# Booster_PA_PREAMP.net
KiCad netlist of a schematic drawn in Altium Designer
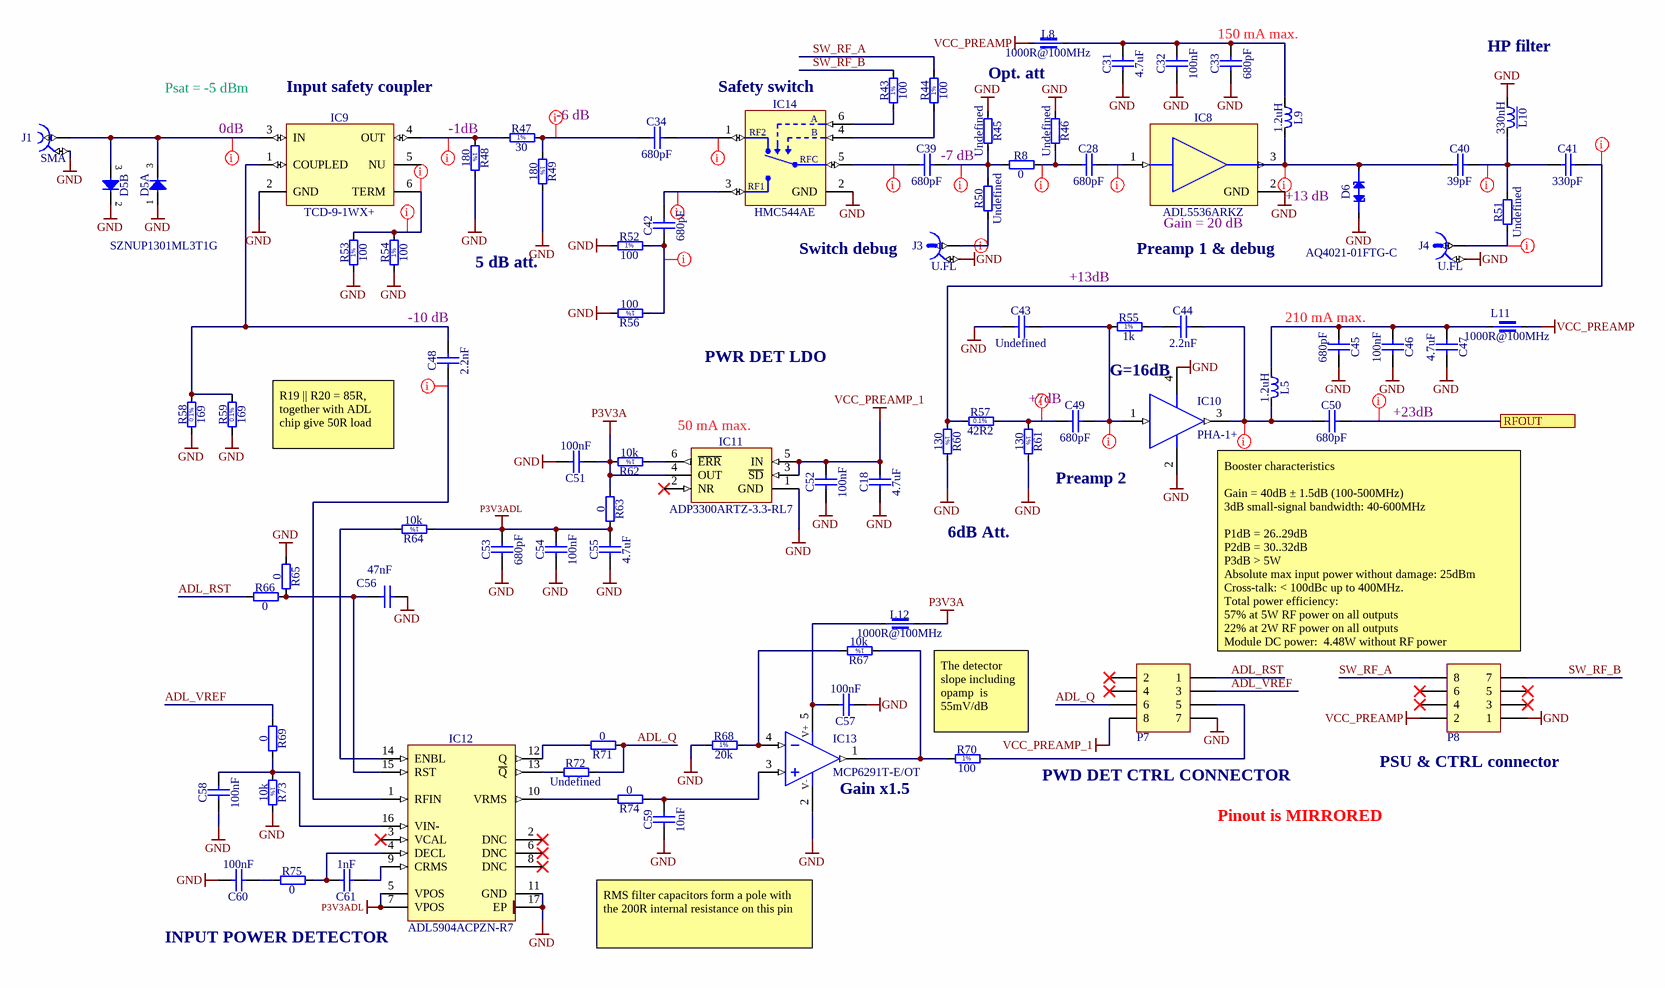
[diagram p0: Booster_PA_PREAMP.SchDoc]

(export (version "E")
  (design (tool "Eeschema 10.0.6"))
  (components
    (comp (ref "C18")
      (value "4.7uF")
      (footprint "CAPC1709X95N")
      (description "Non-polarised capacitor")
      (fields
        (field (name "MANUFACTURER") "GENERIC")
        (field (name "MANUFACTURER PART NUMBER") "CC0603_4.7UF_16V_10%_X5R")
        (field (name "AUTHOR") "CERN DEM JLC")
      )
      (libsource (lib "Capacitors") (part "Capacitor - non polarized"))
    )
    (comp (ref "C28")
      (value "680pF")
      (footprint "CAPC1608X87N")
      (description "Non-polarised capacitor")
      (fields
        (field (name "PART NUMBER") "CC0603_680PF_50V_5%_NP0")
        (field (name "VOLTAGE") "50V")
        (field (name "AUTHOR") "CERN DEM JLC")
      )
      (libsource (lib "Capacitors") (part "Capacitor - non polarized"))
    )
    (comp (ref "C31")
      (value "4.7uF")
      (footprint "CAPC1709X95N")
      (description "Non-polarised capacitor")
      (fields
        (field (name "MANUFACTURER") "GENERIC")
        (field (name "MANUFACTURER PART NUMBER") "CC0603_4.7UF_16V_10%_X5R")
        (field (name "AUTHOR") "CERN DEM JLC")
      )
      (libsource (lib "Capacitors") (part "Capacitor - non polarized"))
    )
    (comp (ref "C32")
      (value "100nF")
      (footprint "CAPC1608X87N")
      (description "Non-polarised capacitor")
      (fields
        (field (name "MANUFACTURER") "GENERIC")
        (field (name "MANUFACTURER PART NUMBER") "CC0603_100NF_50V_10%_X7R")
        (field (name "AUTHOR") "CERN DEM JLC")
      )
      (libsource (lib "Capacitors") (part "Capacitor - non polarized"))
    )
    (comp (ref "C33")
      (value "680pF")
      (footprint "CAPC1608X87N")
      (description "Non-polarised capacitor")
      (fields
        (field (name "PART NUMBER") "CC0603_680PF_50V_5%_NP0")
        (field (name "VOLTAGE") "50V")
        (field (name "AUTHOR") "CERN DEM JLC")
      )
      (libsource (lib "Capacitors") (part "Capacitor - non polarized"))
    )
    (comp (ref "C34")
      (value "680pF")
      (footprint "CAPC1608X87N")
      (description "Non-polarised capacitor")
      (fields
        (field (name "PART NUMBER") "CC0603_680PF_50V_5%_NP0")
        (field (name "VOLTAGE") "50V")
        (field (name "AUTHOR") "CERN DEM JLC")
      )
      (libsource (lib "Capacitors") (part "Capacitor - non polarized"))
    )
    (comp (ref "C39")
      (value "680pF")
      (footprint "CAPC1608X87N")
      (description "Non-polarised capacitor")
      (fields
        (field (name "PART NUMBER") "CC0603_680PF_50V_5%_NP0")
        (field (name "VOLTAGE") "50V")
        (field (name "AUTHOR") "CERN DEM JLC")
      )
      (libsource (lib "Capacitors") (part "Capacitor - non polarized"))
    )
    (comp (ref "C40")
      (value "39pF")
      (footprint "CAPC1608X87N")
      (description "Non-polarised capacitor")
      (fields
        (field (name "PART NUMBER") "CC0603_39PF_100V_1%_NP0")
        (field (name "VOLTAGE") "100V")
        (field (name "AUTHOR") "GK")
      )
      (libsource (lib "Passives_RC") (part "CC0603_39PF_50V_1%_NP0"))
    )
    (comp (ref "C41")
      (value "330pF")
      (footprint "CAPC1608X87N")
      (description "Non-polarised capacitor")
      (fields
        (field (name "MANUFACTURER") "GENERIC")
        (field (name "MANUFACTURER PART NUMBER") "CC0603_330PF_50V_1%_NP0")
        (field (name "AUTHOR") "CERN DEM MR")
      )
      (libsource (lib "Capacitors") (part "Capacitor - non polarized"))
    )
    (comp (ref "C42")
      (value "680pF")
      (footprint "CAPC1608X87N")
      (description "Non-polarised capacitor")
      (fields
        (field (name "PART NUMBER") "CC0603_680PF_50V_5%_NP0")
        (field (name "VOLTAGE") "50V")
        (field (name "AUTHOR") "CERN DEM JLC")
      )
      (libsource (lib "Capacitors") (part "Capacitor - non polarized"))
    )
    (comp (ref "C43")
      (value "Undefined")
      (footprint "CAPC1608X90N")
      (description "Non-polarised capacitor")
      (fields (field (name "PART NUMBER") "CC0603_NO-VALUE") (field (name "AUTHOR") "CERN DEM MR"))
      (libsource (lib "Capacitors") (part "Capacitor - non polarized"))
    )
    (comp (ref "C44")
      (value "2.2nF")
      (footprint "CAPC1608X87N")
      (description "Non-polarised capacitor")
      (fields
        (field (name "PART NUMBER") "CC0603_2.2NF_50V_5%_C0G")
        (field (name "VOLTAGE") "50V")
        (field (name "AUTHOR") "CERN DEM JMW")
      )
      (libsource (lib "Capacitors") (part "Capacitor - non polarized"))
    )
    (comp (ref "C45")
      (value "680pF")
      (footprint "CAPC1608X87N")
      (description "Non-polarised capacitor")
      (fields
        (field (name "MANUFACTURER") "GENERIC")
        (field (name "MANUFACTURER PART NUMBER") "CC0603_680PF_50V_5%_NP0")
        (field (name "AUTHOR") "CERN DEM JLC")
      )
      (libsource (lib "Capacitors") (part "Capacitor - non polarized"))
    )
    (comp (ref "C46")
      (value "100nF")
      (footprint "CAPC1608X87N")
      (description "Non-polarised capacitor")
      (fields
        (field (name "MANUFACTURER") "GENERIC")
        (field (name "MANUFACTURER PART NUMBER") "CC0603_100NF_50V_10%_X7R")
        (field (name "AUTHOR") "CERN DEM JLC")
      )
      (libsource (lib "Capacitors") (part "Capacitor - non polarized"))
    )
    (comp (ref "C47")
      (value "4.7uF")
      (footprint "CAPC1709X95N")
      (description "Non-polarised capacitor")
      (fields
        (field (name "MANUFACTURER") "GENERIC")
        (field (name "MANUFACTURER PART NUMBER") "CC0603_4.7UF_16V_10%_X5R")
        (field (name "AUTHOR") "CERN DEM JLC")
      )
      (libsource (lib "Capacitors") (part "Capacitor - non polarized"))
    )
    (comp (ref "C48")
      (value "2.2nF")
      (footprint "CAPC1608X87N")
      (description "Non-polarised capacitor")
      (fields
        (field (name "PART NUMBER") "CC0603_2.2NF_50V_5%_C0G")
        (field (name "VOLTAGE") "50V")
        (field (name "AUTHOR") "CERN DEM JMW")
      )
      (libsource (lib "Capacitors") (part "Capacitor - non polarized"))
    )
    (comp (ref "C49")
      (value "680pF")
      (footprint "CAPC1608X87N")
      (description "Non-polarised capacitor")
      (fields
        (field (name "MANUFACTURER") "GENERIC")
        (field (name "MANUFACTURER PART NUMBER") "CC0603_680PF_50V_5%_NP0")
        (field (name "AUTHOR") "CERN DEM JLC")
      )
      (libsource (lib "Capacitors") (part "Capacitor - non polarized"))
    )
    (comp (ref "C50")
      (value "680pF")
      (footprint "CAPC1608X87N")
      (description "Non-polarised capacitor")
      (fields
        (field (name "MANUFACTURER") "GENERIC")
        (field (name "MANUFACTURER PART NUMBER") "CC0603_680PF_50V_5%_NP0")
        (field (name "AUTHOR") "CERN DEM JLC")
      )
      (libsource (lib "Capacitors") (part "Capacitor - non polarized"))
    )
    (comp (ref "C51")
      (value "100nF")
      (footprint "CAPC1608X87N")
      (description "Non-polarised capacitor")
      (fields
        (field (name "MANUFACTURER") "GENERIC")
        (field (name "MANUFACTURER PART NUMBER") "CC0603_100NF_50V_10%_X7R")
        (field (name "AUTHOR") "CERN DEM JLC")
      )
      (libsource (lib "Capacitors") (part "Capacitor - non polarized"))
    )
    (comp (ref "C52")
      (value "100nF")
      (footprint "CAPC1608X87N")
      (description "Non-polarised capacitor")
      (fields
        (field (name "MANUFACTURER") "GENERIC")
        (field (name "MANUFACTURER PART NUMBER") "CC0603_100NF_50V_10%_X7R")
        (field (name "AUTHOR") "CERN DEM JLC")
      )
      (libsource (lib "Capacitors") (part "Capacitor - non polarized"))
    )
    (comp (ref "C53")
      (value "680pF")
      (footprint "CAPC1608X87N")
      (description "Non-polarised capacitor")
      (fields
        (field (name "MANUFACTURER") "GENERIC")
        (field (name "MANUFACTURER PART NUMBER") "CC0603_680PF_50V_5%_NP0")
        (field (name "AUTHOR") "CERN DEM JLC")
      )
      (libsource (lib "Capacitors") (part "Capacitor - non polarized"))
    )
    (comp (ref "C54")
      (value "100nF")
      (footprint "CAPC1608X87N")
      (description "Non-polarised capacitor")
      (fields
        (field (name "MANUFACTURER") "GENERIC")
        (field (name "MANUFACTURER PART NUMBER") "CC0603_100NF_50V_10%_X7R")
        (field (name "AUTHOR") "CERN DEM JLC")
      )
      (libsource (lib "Capacitors") (part "Capacitor - non polarized"))
    )
    (comp (ref "C55")
      (value "4.7uF")
      (footprint "CAPC1709X95N")
      (description "Non-polarised capacitor")
      (fields
        (field (name "MANUFACTURER") "GENERIC")
        (field (name "MANUFACTURER PART NUMBER") "CC0603_4.7UF_16V_10%_X5R")
        (field (name "AUTHOR") "CERN DEM JLC")
      )
      (libsource (lib "Capacitors") (part "Capacitor - non polarized"))
    )
    (comp (ref "C56")
      (value "47nF")
      (footprint "CAPC1608X87N")
      (description "Non-polarised capacitor")
      (fields
        (field (name "PART NUMBER") "CC0603_47NF_25V_10%_X7R")
        (field (name "VOLTAGE") "25V")
        (field (name "AUTHOR") "CERN DEM JLC")
      )
      (libsource (lib "Capacitors") (part "Capacitor - non polarized"))
    )
    (comp (ref "C57")
      (value "100nF")
      (footprint "CAPC1608X87N")
      (description "Non-polarised capacitor")
      (fields
        (field (name "MANUFACTURER") "GENERIC")
        (field (name "MANUFACTURER PART NUMBER") "CC0603_100NF_50V_10%_X7R")
        (field (name "AUTHOR") "CERN DEM JLC")
      )
      (libsource (lib "Capacitors") (part "Capacitor - non polarized"))
    )
    (comp (ref "C58")
      (value "100nF")
      (footprint "CAPC1608X87N")
      (description "Non-polarised capacitor")
      (fields
        (field (name "MANUFACTURER") "GENERIC")
        (field (name "MANUFACTURER PART NUMBER") "CC0603_100NF_50V_10%_X7R")
        (field (name "AUTHOR") "CERN DEM JLC")
      )
      (libsource (lib "Capacitors") (part "Capacitor - non polarized"))
    )
    (comp (ref "C59")
      (value "10nF")
      (footprint "CAPC1005X55N")
      (description "Non-polarised capacitor")
      (fields
        (field (name "MANUFACTURER") "GENERIC")
        (field (name "MANUFACTURER PART NUMBER") "CC0402_10NF_25V_10%_X7R")
        (field (name "AUTHOR") "CERN DEM JLC")
      )
      (libsource (lib "Capacitors") (part "Capacitor - non polarized"))
    )
    (comp (ref "C60")
      (value "100nF")
      (footprint "CAPC1608X87N")
      (description "Non-polarised capacitor")
      (fields
        (field (name "MANUFACTURER") "GENERIC")
        (field (name "MANUFACTURER PART NUMBER") "CC0603_100NF_50V_10%_X7R")
        (field (name "AUTHOR") "CERN DEM JLC")
      )
      (libsource (lib "Capacitors") (part "Capacitor - non polarized"))
    )
    (comp (ref "C61")
      (value "1nF")
      (footprint "CAPC1005X55N")
      (description "Non-polarised capacitor")
      (fields
        (field (name "PART NUMBER") "CC0402_1NF_50V_10%_X7R")
        (field (name "VOLTAGE") "50V")
        (field (name "AUTHOR") "CERN DEM JLC")
      )
      (libsource (lib "Capacitors") (part "Capacitor - non polarized"))
    )
    (comp (ref "D5")
      (value "SZNUP1301ML3T1G")
      (footprint "SOT95P240X110-3N")
      (description "Low Capacitance Diode Array for ESD Protection in a Single Data Line")
      (fields (field (name "VOLTAGE") "70V") (field (name "POWER") "215mA") (field (name "AUTHOR") "GK"))
      (libsource (lib "Diodes") (part "D_TVS_SZNUP1301ML3T1G"))
    )
    (comp (ref "D6")
      (value "AQ4021-01FTG-C")
      (footprint "SOD2513X114N")
      (description "6V Bi-directional,ESD Protection for Transient Voltage Suppressor Diode")
      (fields (field (name "VOLTAGE") "6V") (field (name "POWER") "450W") (field (name "AUTHOR") "GK"))
      (libsource (lib "Diodes") (part "D_TVS_AQ4021-01FTG-C"))
    )
    (comp (ref "IC8")
      (value "ADL5536ARKZ")
      (footprint "ANALOG-DEVICES_SOT-89(RK-3)")
      (description "20MHz to 1GHz IF Gain Block")
      (fields (field (name "MANUFACTURER") "ANALOG DEVICES") (field (name "AUTHOR") "CERN DEM BC"))
      (libsource (lib "ICs And Semiconductors") (part "ADL5536"))
    )
    (comp (ref "IC9")
      (value "TCD-9-1WX+")
      (footprint "MINI-CIRCUITS_DB1627")
      (description "50 Ohm, 5 To 2000MHz, Directional Coupler")
      (fields (field (name "MANUFACTURER") "MINI-CIRCUITS") (field (name "AUTHOR") "CERN DEM BC"))
      (libsource (lib "ICs And Semiconductors") (part "TCD-9-1W"))
    )
    (comp (ref "IC10")
      (value "PHA-1+")
      (footprint "MINI-CIRCUITS_DF782")
      (description "Monolithic Amplifier")
      (fields (field (name "MANUFACTURER") "MINI-CIRCUITS") (field (name "AUTHOR") "CERN DEM BC"))
      (libsource (lib "ICs And Semiconductors") (part "Monolithic Amplifier Type 1"))
    )
    (comp (ref "IC11")
      (value "ADP3300ARTZ-3.3-RL7")
      (footprint "SOT95P280X145-6N")
      (description "High Accuracy anyCAP® 50 mA Low Dropout Linear Regulator")
      (fields (field (name "MANUFACTURER") "ANALOG DEVICES") (field (name "AUTHOR") "CERN DEM JLC"))
      (libsource (lib "ICs And Semiconductors") (part "ADP3300ARTZ"))
    )
    (comp (ref "IC12")
      (value "ADL5904ACPZN-R7")
      (footprint "QFN50P300X300X80-17N-S175")
      (description "DC to 6 GHz, 45 dB TruPwr Detector With Envelope Threshold Detection")
      (fields (field (name "MANUFACTURER") "ANALOG DEVICES") (field (name "AUTHOR") "CERN DEM MR"))
      (libsource (lib "ICs And Semiconductors") (part "ADL5904"))
    )
    (comp (ref "IC13")
      (value "MCP6291T-E/OT")
      (footprint "SOT95P270X145-5N")
      (description "Operational Amplifier")
      (fields (field (name "MANUFACTURER") "MICROCHIP TECHNOLOGY") (field (name "AUTHOR") "CERN DEM BC"))
      (libsource (lib "ICs And Semiconductors") (part "Operational Amplifier Type7"))
    )
    (comp (ref "IC14")
      (value "HMC544AE")
      (footprint "SOT95P280X145-6N")
      (description "GaAs MMIC T/R Switch DC - 4 GHz")
      (fields (field (name "MANUFACTURER") "ANALOG DEVICES") (field (name "AUTHOR") "CERN DEM MR"))
      (libsource (lib "ICs And Semiconductors") (part "HMC544AE"))
    )
    (comp (ref "J1")
      (value "SMA")
      (footprint "LINK_CONSMA002-SMD-G")
      (fields
        (field (name "PART NUMBER") "LINK_CONSMA002-SMD-G")
        (field (name "MANUFACTURER") "LINK TECHNOLOGIES")
        (field (name "MANUFACTURER PART NUMBER") "CONSMA002-SMD-G")
        (field (name "AUTHOR") "CERN DEM BC")
      )
      (libsource (lib "Connectors") (part "Coax_1Female_1Shield"))
    )
    (comp (ref "J3")
      (value "U.FL")
      (footprint "HIROSE_U.FL-R-SMT-1(10)")
      (fields
        (field (name "PART NUMBER") "HIROSE_U.FL-R-SMT-1(10)")
        (field (name "MANUFACTURER") "HIROSE (HRS)")
        (field (name "MANUFACTURER PART NUMBER") "U.FL-R-SMT-1(10)")
        (field (name "AUTHOR") "CERN DEM JLC")
      )
      (libsource (lib "Connectors") (part "Coax_1Male_1Shield"))
    )
    (comp (ref "J4")
      (value "U.FL")
      (footprint "HIROSE_U.FL-R-SMT-1(10)")
      (fields
        (field (name "PART NUMBER") "HIROSE_U.FL-R-SMT-1(10)")
        (field (name "MANUFACTURER") "HIROSE (HRS)")
        (field (name "MANUFACTURER PART NUMBER") "U.FL-R-SMT-1(10)")
        (field (name "AUTHOR") "CERN DEM JLC")
      )
      (libsource (lib "Connectors") (part "Coax_1Male_1Shield"))
    )
    (comp (ref "L5")
      (value "1.2uH")
      (footprint "IND_TDK_ADL2012")
      (description "Inductor")
      (fields
        (field (name "PART NUMBER") "IND0805_TDK_ADL2012S-1R2M-T01")
        (field (name "POWER") "400mA")
        (field (name "AUTHOR") "GK")
      )
      (libsource (lib "Inductors_Transformers") (part "IND0805_TDK_ADL2012S-1R2M-T01"))
    )
    (comp (ref "L8")
      (value "1000R@100MHz")
      (footprint "INDC1608X95N")
      (fields
        (field (name "MANUFACTURER") "MURATA")
        (field (name "MANUFACTURER PART NUMBER") "BLM18HE102SN1")
        (field (name "PART NUMBER") "IND0603_MURATA_BLM18HE102SN1")
        (field (name "AUTHOR") "CERN DEM JLC")
      )
      (libsource (lib "Inductors & Transformers") (part "Ferrite Bead"))
    )
    (comp (ref "L9")
      (value "1.2uH")
      (footprint "IND_TDK_ADL2012")
      (description "Inductor")
      (fields
        (field (name "PART NUMBER") "IND0805_TDK_ADL2012S-1R2M-T01")
        (field (name "POWER") "400mA")
        (field (name "AUTHOR") "GK")
      )
      (libsource (lib "Inductors_Transformers") (part "IND0805_TDK_ADL2012S-1R2M-T01"))
    )
    (comp (ref "L10")
      (value "330nH")
      (footprint "IND_COILCRAFT_0603LS")
      (description "Inductor With Core")
      (fields
        (field (name "PART NUMBER") "IND_330NH_2%_COILCRAFT_0603LS")
        (field (name "POWER") "560mA")
        (field (name "AUTHOR") "CERN DEM BC")
      )
      (libsource (lib "Inductors & Transformers") (part "Inductor With Magnetic core"))
    )
    (comp (ref "L11")
      (value "1000R@100MHz")
      (footprint "INDC1608X95N")
      (fields
        (field (name "MANUFACTURER") "MURATA")
        (field (name "MANUFACTURER PART NUMBER") "BLM18HE102SN1")
        (field (name "PART NUMBER") "IND0603_MURATA_BLM18HE102SN1")
        (field (name "AUTHOR") "CERN DEM JLC")
      )
      (libsource (lib "Inductors & Transformers") (part "Ferrite Bead"))
    )
    (comp (ref "L12")
      (value "1000R@100MHz")
      (footprint "INDC1608X95N")
      (fields
        (field (name "MANUFACTURER") "MURATA")
        (field (name "MANUFACTURER PART NUMBER") "BLM18HE102SN1")
        (field (name "PART NUMBER") "IND0603_MURATA_BLM18HE102SN1")
        (field (name "AUTHOR") "CERN DEM JLC")
      )
      (libsource (lib "Inductors & Transformers") (part "Ferrite Bead"))
    )
    (comp (ref "P7")
      (value "ZL264-8DG")
      (footprint "HDR2X4_SMD")
      (description "Header, 4-Pin, Dual Row")
      (libsource (lib "onyks") (part "HDR2X4"))
    )
    (comp (ref "P8")
      (value "ZL264-8DG")
      (footprint "HDR2X4_SMD")
      (description "Header, 4-Pin, Dual Row")
      (libsource (lib "") (part "HDR2X4_1"))
    )
    (comp (ref "R8")
      (value "0")
      (footprint "RESC1005X40N")
      (description "Resistor")
      (fields
        (field (name "MANUFACTURER") "GENERIC")
        (field (name "MANUFACTURER PART NUMBER") "R0402_0R_JUMPER")
        (field (name "AUTHOR") "CERN DEM JLC")
      )
      (libsource (lib "Resistors") (part "Resistor"))
    )
    (comp (ref "R43")
      (value "100")
      (footprint "RESC1608X55N")
      (description "Resistor - 1%")
      (fields
        (field (name "MANUFACTURER") "GENERIC")
        (field (name "MANUFACTURER PART NUMBER") "R0603_100R_1%_0.1W_100PPM")
        (field (name "AUTHOR") "CERN DEM JLC")
      )
      (libsource (lib "Resistors") (part "Resistor - 1%"))
    )
    (comp (ref "R44")
      (value "100")
      (footprint "RESC1608X55N")
      (description "Resistor - 1%")
      (fields
        (field (name "MANUFACTURER") "GENERIC")
        (field (name "MANUFACTURER PART NUMBER") "R0603_100R_1%_0.1W_100PPM")
        (field (name "AUTHOR") "CERN DEM JLC")
      )
      (libsource (lib "Resistors") (part "Resistor - 1%"))
    )
    (comp (ref "R45")
      (value "Undefined")
      (footprint "RESC1608X55N")
      (description "Resistor")
      (fields
        (field (name "MANUFACTURER PART NUMBER") "R0603_NO-VALUE")
        (field (name "AUTHOR") "CERN DEM JLC")
      )
      (libsource (lib "Resistors") (part "Resistor"))
    )
    (comp (ref "R46")
      (value "Undefined")
      (footprint "RESC1608X55N")
      (description "Resistor")
      (fields
        (field (name "MANUFACTURER PART NUMBER") "R0603_NO-VALUE")
        (field (name "AUTHOR") "CERN DEM JLC")
      )
      (libsource (lib "Resistors") (part "Resistor"))
    )
    (comp (ref "R47")
      (value "30")
      (footprint "RESC1608X55N")
      (description "Resistor - 1%")
      (fields
        (field (name "PART NUMBER") "R0603_30R_1%_0.1W_100PPM")
        (field (name "POWER") "0.1W")
        (field (name "AUTHOR") "CERN DEM JLC")
      )
      (libsource (lib "Resistors") (part "Resistor - 1%"))
    )
    (comp (ref "R48")
      (value "180")
      (footprint "RESC1608X55N")
      (description "Resistor - 1%")
      (fields
        (field (name "MANUFACTURER") "GENERIC")
        (field (name "MANUFACTURER PART NUMBER") "R0603_180R_1%_0.1W_100PPM")
        (field (name "AUTHOR") "CERN DEM JLC")
      )
      (libsource (lib "Resistors") (part "Resistor - 1%"))
    )
    (comp (ref "R49")
      (value "180")
      (footprint "RESC1608X55N")
      (description "Resistor - 1%")
      (fields
        (field (name "MANUFACTURER") "GENERIC")
        (field (name "MANUFACTURER PART NUMBER") "R0603_180R_1%_0.1W_100PPM")
        (field (name "AUTHOR") "CERN DEM JLC")
      )
      (libsource (lib "Resistors") (part "Resistor - 1%"))
    )
    (comp (ref "R50")
      (value "Undefined")
      (footprint "RESC1608X55N")
      (description "Resistor")
      (fields
        (field (name "MANUFACTURER PART NUMBER") "R0603_NO-VALUE")
        (field (name "AUTHOR") "CERN DEM JLC")
      )
      (libsource (lib "Resistors") (part "Resistor"))
    )
    (comp (ref "R51")
      (value "Undefined")
      (footprint "RESC1608X55N")
      (description "Resistor")
      (fields
        (field (name "MANUFACTURER PART NUMBER") "R0603_NO-VALUE")
        (field (name "AUTHOR") "CERN DEM JLC")
      )
      (libsource (lib "Resistors") (part "Resistor"))
    )
    (comp (ref "R52")
      (value "100")
      (footprint "RESC1608X55N")
      (description "Resistor - 1%")
      (fields
        (field (name "MANUFACTURER") "GENERIC")
        (field (name "MANUFACTURER PART NUMBER") "R0603_100R_1%_0.1W_100PPM")
        (field (name "AUTHOR") "CERN DEM JLC")
      )
      (libsource (lib "Resistors") (part "Resistor - 1%"))
    )
    (comp (ref "R53")
      (value "100")
      (footprint "RESC1608X55N")
      (description "Resistor - 1%")
      (fields
        (field (name "MANUFACTURER") "GENERIC")
        (field (name "MANUFACTURER PART NUMBER") "R0603_100R_1%_0.1W_100PPM")
        (field (name "AUTHOR") "CERN DEM JLC")
      )
      (libsource (lib "Resistors") (part "Resistor - 1%"))
    )
    (comp (ref "R54")
      (value "100")
      (footprint "RESC1608X55N")
      (description "Resistor - 1%")
      (fields
        (field (name "MANUFACTURER") "GENERIC")
        (field (name "MANUFACTURER PART NUMBER") "R0603_100R_1%_0.1W_100PPM")
        (field (name "AUTHOR") "CERN DEM JLC")
      )
      (libsource (lib "Resistors") (part "Resistor - 1%"))
    )
    (comp (ref "R55")
      (value "1k")
      (footprint "RESC1608X55N")
      (description "Resistor - 1%")
      (fields
        (field (name "MANUFACTURER") "GENERIC")
        (field (name "MANUFACTURER PART NUMBER") "R0603_1K_1%_0.1W_100PPM")
        (field (name "AUTHOR") "CERN DEM JLC")
      )
      (libsource (lib "Resistors") (part "Resistor - 1%"))
    )
    (comp (ref "R56")
      (value "100")
      (footprint "RESC1608X55N")
      (description "Resistor - 1%")
      (fields
        (field (name "MANUFACTURER") "GENERIC")
        (field (name "MANUFACTURER PART NUMBER") "R0603_100R_1%_0.1W_100PPM")
        (field (name "AUTHOR") "CERN DEM JLC")
      )
      (libsource (lib "Resistors") (part "Resistor - 1%"))
    )
    (comp (ref "R57")
      (value "42R2")
      (footprint "RESC1608X55N")
      (description "Resistor - 0.1%")
      (fields
        (field (name "PART NUMBER") "R0603_42R2_0.1%_0.063W_10PPM")
        (field (name "POWER") "0.063W")
        (field (name "AUTHOR") "CERN DEM JLC")
      )
      (libsource (lib "Resistors") (part "Resistor - 0.1%"))
    )
    (comp (ref "R58")
      (value "169")
      (footprint "RESC1608X55N")
      (description "Resistor - 0.1%")
      (fields
        (field (name "PART NUMBER") "R0603_169R_0.1%_0.063W_10PPM")
        (field (name "POWER") "0.063W")
        (field (name "AUTHOR") "CERN DEM JLC")
      )
      (libsource (lib "Resistors") (part "Resistor - 0.1%"))
    )
    (comp (ref "R59")
      (value "169")
      (footprint "RESC1608X55N")
      (description "Resistor - 0.1%")
      (fields
        (field (name "PART NUMBER") "R0603_169R_0.1%_0.063W_10PPM")
        (field (name "POWER") "0.063W")
        (field (name "AUTHOR") "CERN DEM JLC")
      )
      (libsource (lib "Resistors") (part "Resistor - 0.1%"))
    )
    (comp (ref "R60")
      (value "130")
      (footprint "RESC1608X55N")
      (description "Resistor - 1%")
      (fields
        (field (name "MANUFACTURER") "GENERIC")
        (field (name "MANUFACTURER PART NUMBER") "R0603_130R_1%_0.1W_100PPM")
        (field (name "AUTHOR") "CERN DEM JLC")
      )
      (libsource (lib "Resistors") (part "Resistor - 1%"))
    )
    (comp (ref "R61")
      (value "130")
      (footprint "RESC1608X55N")
      (description "Resistor - 1%")
      (fields
        (field (name "MANUFACTURER") "GENERIC")
        (field (name "MANUFACTURER PART NUMBER") "R0603_130R_1%_0.1W_100PPM")
        (field (name "AUTHOR") "CERN DEM JLC")
      )
      (libsource (lib "Resistors") (part "Resistor - 1%"))
    )
    (comp (ref "R62")
      (value "10k")
      (footprint "RESC1005X40N")
      (description "Resistor - 1%")
      (fields
        (field (name "MANUFACTURER") "GENERIC")
        (field (name "MANUFACTURER PART NUMBER") "R0402_10K_1%_0.0625W_100PPM")
        (field (name "AUTHOR") "CERN DEM JLC")
      )
      (libsource (lib "Resistors") (part "Resistor - 1%"))
    )
    (comp (ref "R63")
      (value "0")
      (footprint "RESC1005X40N")
      (description "Resistor")
      (fields
        (field (name "MANUFACTURER") "GENERIC")
        (field (name "MANUFACTURER PART NUMBER") "R0402_0R_JUMPER")
        (field (name "AUTHOR") "CERN DEM JLC")
      )
      (libsource (lib "Resistors") (part "Resistor"))
    )
    (comp (ref "R64")
      (value "10k")
      (footprint "RESC1005X40N")
      (description "Resistor - 1%")
      (fields
        (field (name "MANUFACTURER") "GENERIC")
        (field (name "MANUFACTURER PART NUMBER") "R0402_10K_1%_0.0625W_100PPM")
        (field (name "AUTHOR") "CERN DEM JLC")
      )
      (libsource (lib "Resistors") (part "Resistor - 1%"))
    )
    (comp (ref "R65")
      (value "0")
      (footprint "RESC1005X40N")
      (description "Resistor")
      (fields
        (field (name "MANUFACTURER") "GENERIC")
        (field (name "MANUFACTURER PART NUMBER") "R0402_0R_JUMPER")
        (field (name "AUTHOR") "CERN DEM JLC")
      )
      (libsource (lib "Resistors") (part "Resistor"))
    )
    (comp (ref "R66")
      (value "0")
      (footprint "RESC1005X40N")
      (description "Resistor")
      (fields
        (field (name "MANUFACTURER") "GENERIC")
        (field (name "MANUFACTURER PART NUMBER") "R0402_0R_JUMPER")
        (field (name "AUTHOR") "CERN DEM JLC")
      )
      (libsource (lib "Resistors") (part "Resistor"))
    )
    (comp (ref "R67")
      (value "10k")
      (footprint "RESC1005X40N")
      (description "Resistor - 1%")
      (fields
        (field (name "MANUFACTURER") "GENERIC")
        (field (name "MANUFACTURER PART NUMBER") "R0402_10K_1%_0.0625W_100PPM")
        (field (name "AUTHOR") "CERN DEM JLC")
      )
      (libsource (lib "Resistors") (part "Resistor - 1%"))
    )
    (comp (ref "R68")
      (value "20k")
      (footprint "RESC1608X55N")
      (description "Resistor - 1%")
      (fields
        (field (name "PART NUMBER") "R0603_20K_1%_0.1W_100PPM")
        (field (name "POWER") "0.1W")
        (field (name "AUTHOR") "CERN DEM JLC")
      )
      (libsource (lib "Resistors") (part "Resistor - 1%"))
    )
    (comp (ref "R69")
      (value "0")
      (footprint "RESC1005X40N")
      (description "Resistor")
      (fields
        (field (name "MANUFACTURER") "GENERIC")
        (field (name "MANUFACTURER PART NUMBER") "R0402_0R_JUMPER")
        (field (name "AUTHOR") "CERN DEM JLC")
      )
      (libsource (lib "Resistors") (part "Resistor"))
    )
    (comp (ref "R70")
      (value "100")
      (footprint "RESC1608X55N")
      (description "Resistor - 1%")
      (fields
        (field (name "MANUFACTURER") "GENERIC")
        (field (name "MANUFACTURER PART NUMBER") "R0603_100R_1%_0.1W_100PPM")
        (field (name "AUTHOR") "CERN DEM JLC")
      )
      (libsource (lib "Resistors") (part "Resistor - 1%"))
    )
    (comp (ref "R71")
      (value "0")
      (footprint "RESC1005X40N")
      (description "Resistor")
      (fields
        (field (name "MANUFACTURER") "GENERIC")
        (field (name "MANUFACTURER PART NUMBER") "R0402_0R_JUMPER")
        (field (name "AUTHOR") "CERN DEM JLC")
      )
      (libsource (lib "Resistors") (part "Resistor"))
    )
    (comp (ref "R72")
      (value "Undefined")
      (footprint "RESC1608X55N")
      (description "Resistor")
      (fields
        (field (name "MANUFACTURER PART NUMBER") "R0603_NO-VALUE")
        (field (name "AUTHOR") "CERN DEM JLC")
      )
      (libsource (lib "Resistors") (part "Resistor"))
    )
    (comp (ref "R73")
      (value "10k")
      (footprint "RESC1005X40N")
      (description "Resistor - 1%")
      (fields
        (field (name "MANUFACTURER") "GENERIC")
        (field (name "MANUFACTURER PART NUMBER") "R0402_10K_1%_0.0625W_100PPM")
        (field (name "AUTHOR") "CERN DEM JLC")
      )
      (libsource (lib "Resistors") (part "Resistor - 1%"))
    )
    (comp (ref "R74")
      (value "0")
      (footprint "RESC1005X40N")
      (description "Resistor")
      (fields
        (field (name "MANUFACTURER") "GENERIC")
        (field (name "MANUFACTURER PART NUMBER") "R0402_0R_JUMPER")
        (field (name "AUTHOR") "CERN DEM JLC")
      )
      (libsource (lib "Resistors") (part "Resistor"))
    )
    (comp (ref "R75")
      (value "0")
      (footprint "RESC1005X40N")
      (description "Resistor")
      (fields
        (field (name "MANUFACTURER") "GENERIC")
        (field (name "MANUFACTURER PART NUMBER") "R0402_0R_JUMPER")
        (field (name "AUTHOR") "CERN DEM JLC")
      )
      (libsource (lib "Resistors") (part "Resistor"))
    )
  )
  (nets
    (net (code "1") (name "/ADL_Q") (class "Default")
      (node (ref "P7") (pin "6") (pinfunction "6_6") (pintype "passive"))
      (node (ref "R71") (pin "1") (pinfunction "1_1") (pintype "passive"))
      (node (ref "R72") (pin "2") (pinfunction "2_2") (pintype "passive"))
    )
    (net (code "2") (name "/ADL_RST") (class "Default")
      (node (ref "P7") (pin "1") (pinfunction "1_1") (pintype "passive"))
      (node (ref "R66") (pin "1") (pinfunction "1_1") (pintype "passive"))
    )
    (net (code "3") (name "/ADL_VREF") (class "Default")
      (node (ref "P7") (pin "3") (pinfunction "3_3") (pintype "passive"))
      (node (ref "R69") (pin "1") (pinfunction "1_1") (pintype "passive"))
    )
    (net (code "4") (name "/RFOUT") (class "Default")
      (node (ref "C50") (pin "2") (pinfunction "2_2") (pintype "passive"))
    )
    (net (code "5") (name "/SW_RF_A") (class "Default")
      (node (ref "P8") (pin "8") (pinfunction "8_8") (pintype "passive"))
      (node (ref "R44") (pin "2") (pinfunction "2_2") (pintype "passive"))
    )
    (net (code "6") (name "/SW_RF_B") (class "Default")
      (node (ref "P8") (pin "7") (pinfunction "7_7") (pintype "passive"))
      (node (ref "R43") (pin "2") (pinfunction "2_2") (pintype "passive"))
    )
    (net (code "7") (name "GND") (class "Default")
      (node (ref "C18") (pin "1") (pinfunction "1_1") (pintype "passive"))
      (node (ref "C31") (pin "1") (pinfunction "1_1") (pintype "passive"))
      (node (ref "C32") (pin "1") (pinfunction "1_1") (pintype "passive"))
      (node (ref "C33") (pin "1") (pinfunction "1_1") (pintype "passive"))
      (node (ref "C43") (pin "1") (pinfunction "1_1") (pintype "passive"))
      (node (ref "C45") (pin "1") (pinfunction "1_1") (pintype "passive"))
      (node (ref "C46") (pin "1") (pinfunction "1_1") (pintype "passive"))
      (node (ref "C47") (pin "1") (pinfunction "1_1") (pintype "passive"))
      (node (ref "C51") (pin "2") (pinfunction "2_2") (pintype "passive"))
      (node (ref "C52") (pin "1") (pinfunction "1_1") (pintype "passive"))
      (node (ref "C53") (pin "1") (pinfunction "1_1") (pintype "passive"))
      (node (ref "C54") (pin "1") (pinfunction "1_1") (pintype "passive"))
      (node (ref "C55") (pin "1") (pinfunction "1_1") (pintype "passive"))
      (node (ref "C56") (pin "2") (pinfunction "2_2") (pintype "passive"))
      (node (ref "C57") (pin "1") (pinfunction "1_1") (pintype "passive"))
      (node (ref "C58") (pin "1") (pinfunction "1_1") (pintype "passive"))
      (node (ref "C59") (pin "1") (pinfunction "1_1") (pintype "passive"))
      (node (ref "C60") (pin "2") (pinfunction "2_2") (pintype "passive"))
      (node (ref "D5") (pin "1") (pinfunction "A_1") (pintype "passive"))
      (node (ref "D5") (pin "2") (pinfunction "C_2") (pintype "passive"))
      (node (ref "D6") (pin "1") (pinfunction "C_1") (pintype "passive"))
      (node (ref "IC10") (pin "2") (pinfunction "GND_2") (pintype "power_in"))
      (node (ref "IC10") (pin "4") (pinfunction "GND_4") (pintype "power_in"))
      (node (ref "IC11") (pin "1") (pinfunction "GND_1") (pintype "power_in"))
      (node (ref "IC12") (pin "11") (pinfunction "GND_11") (pintype "power_in"))
      (node (ref "IC12") (pin "17") (pinfunction "EP_17") (pintype "power_in"))
      (node (ref "IC13") (pin "2") (pinfunction "V-_2") (pintype "power_in"))
      (node (ref "IC14") (pin "2") (pinfunction "GND_2") (pintype "power_in"))
      (node (ref "IC8") (pin "2") (pinfunction "GND_2") (pintype "power_in"))
      (node (ref "IC9") (pin "2") (pinfunction "GND_2") (pintype "power_in"))
      (node (ref "J1") (pin "2") (pinfunction "2_2") (pintype "bidirectional"))
      (node (ref "J3") (pin "2") (pinfunction "2_2") (pintype "bidirectional"))
      (node (ref "J4") (pin "2") (pinfunction "2_2") (pintype "bidirectional"))
      (node (ref "L10") (pin "1") (pinfunction "1_1") (pintype "passive"))
      (node (ref "P7") (pin "7") (pinfunction "7_7") (pintype "passive"))
      (node (ref "P8") (pin "1") (pinfunction "1_1") (pintype "passive"))
      (node (ref "R45") (pin "1") (pinfunction "1_1") (pintype "passive"))
      (node (ref "R46") (pin "1") (pinfunction "1_1") (pintype "passive"))
      (node (ref "R48") (pin "2") (pinfunction "2_2") (pintype "passive"))
      (node (ref "R49") (pin "2") (pinfunction "2_2") (pintype "passive"))
      (node (ref "R52") (pin "1") (pinfunction "1_1") (pintype "passive"))
      (node (ref "R53") (pin "1") (pinfunction "1_1") (pintype "passive"))
      (node (ref "R54") (pin "1") (pinfunction "1_1") (pintype "passive"))
      (node (ref "R56") (pin "2") (pinfunction "2_2") (pintype "passive"))
      (node (ref "R58") (pin "1") (pinfunction "1_1") (pintype "passive"))
      (node (ref "R59") (pin "1") (pinfunction "1_1") (pintype "passive"))
      (node (ref "R60") (pin "2") (pinfunction "2_2") (pintype "passive"))
      (node (ref "R61") (pin "2") (pinfunction "2_2") (pintype "passive"))
      (node (ref "R65") (pin "1") (pinfunction "1_1") (pintype "passive"))
      (node (ref "R68") (pin "1") (pinfunction "1_1") (pintype "passive"))
      (node (ref "R73") (pin "2") (pinfunction "2_2") (pintype "passive"))
    )
    (net (code "8") (name "Net-(C28-Pad1)") (class "Default")
      (node (ref "C28") (pin "1") (pinfunction "1_1") (pintype "passive"))
      (node (ref "R46") (pin "2") (pinfunction "2_2") (pintype "passive"))
      (node (ref "R8") (pin "2") (pinfunction "2_2") (pintype "passive"))
    )
    (net (code "9") (name "Net-(C31-Pad2)") (class "Default")
      (node (ref "C31") (pin "2") (pinfunction "2_2") (pintype "passive"))
      (node (ref "C32") (pin "2") (pinfunction "2_2") (pintype "passive"))
      (node (ref "C33") (pin "2") (pinfunction "2_2") (pintype "passive"))
      (node (ref "L8") (pin "2") (pinfunction "2_2") (pintype "passive"))
      (node (ref "L9") (pin "1") (pinfunction "1_1") (pintype "passive"))
    )
    (net (code "10") (name "Net-(C34-Pad1)") (class "Default")
      (node (ref "C34") (pin "1") (pinfunction "1_1") (pintype "passive"))
      (node (ref "R47") (pin "2") (pinfunction "2_2") (pintype "passive"))
      (node (ref "R49") (pin "1") (pinfunction "1_1") (pintype "passive"))
    )
    (net (code "11") (name "Net-(C39-Pad2)") (class "Default")
      (node (ref "C39") (pin "2") (pinfunction "2_2") (pintype "passive"))
      (node (ref "R45") (pin "2") (pinfunction "2_2") (pintype "passive"))
      (node (ref "R50") (pin "2") (pinfunction "2_2") (pintype "passive"))
      (node (ref "R8") (pin "1") (pinfunction "1_1") (pintype "passive"))
    )
    (net (code "12") (name "Net-(C40-Pad2)") (class "Default")
      (node (ref "C40") (pin "2") (pinfunction "2_2") (pintype "passive"))
      (node (ref "C41") (pin "1") (pinfunction "1_1") (pintype "passive"))
      (node (ref "L10") (pin "2") (pinfunction "2_2") (pintype "passive"))
      (node (ref "R51") (pin "2") (pinfunction "2_2") (pintype "passive"))
    )
    (net (code "13") (name "Net-(C41-Pad2)") (class "Default")
      (node (ref "C41") (pin "2") (pinfunction "2_2") (pintype "passive"))
      (node (ref "R57") (pin "1") (pinfunction "1_1") (pintype "passive"))
      (node (ref "R60") (pin "1") (pinfunction "1_1") (pintype "passive"))
    )
    (net (code "14") (name "Net-(C42-Pad1)") (class "Default")
      (node (ref "C42") (pin "1") (pinfunction "1_1") (pintype "passive"))
      (node (ref "R52") (pin "2") (pinfunction "2_2") (pintype "passive"))
      (node (ref "R56") (pin "1") (pinfunction "1_1") (pintype "passive"))
    )
    (net (code "15") (name "Net-(C44-Pad1)") (class "Default")
      (node (ref "C44") (pin "1") (pinfunction "1_1") (pintype "passive"))
      (node (ref "R55") (pin "2") (pinfunction "2_2") (pintype "passive"))
    )
    (net (code "16") (name "Net-(C45-Pad2)") (class "Default")
      (node (ref "C45") (pin "2") (pinfunction "2_2") (pintype "passive"))
      (node (ref "C46") (pin "2") (pinfunction "2_2") (pintype "passive"))
      (node (ref "C47") (pin "2") (pinfunction "2_2") (pintype "passive"))
      (node (ref "L11") (pin "1") (pinfunction "1_1") (pintype "passive"))
      (node (ref "L5") (pin "1") (pinfunction "1_1") (pintype "passive"))
    )
    (net (code "17") (name "Net-(C49-Pad1)") (class "Default")
      (node (ref "C49") (pin "1") (pinfunction "1_1") (pintype "passive"))
      (node (ref "R57") (pin "2") (pinfunction "2_2") (pintype "passive"))
      (node (ref "R61") (pin "1") (pinfunction "1_1") (pintype "passive"))
    )
    (net (code "18") (name "Net-(C60-Pad1)") (class "Default")
      (node (ref "C60") (pin "1") (pinfunction "1_1") (pintype "passive"))
      (node (ref "R75") (pin "1") (pinfunction "1_1") (pintype "passive"))
    )
    (net (code "19") (name "Net-(D5A-COMAC)") (class "Default")
      (node (ref "D5") (pin "3") (pinfunction "COMAC_3") (pintype "passive"))
      (node (ref "IC9") (pin "3") (pinfunction "IN_3") (pintype "bidirectional"))
      (node (ref "J1") (pin "1") (pinfunction "1_1") (pintype "bidirectional"))
    )
    (net (code "20") (name "Net-(D6-A)") (class "Default")
      (node (ref "C40") (pin "1") (pinfunction "1_1") (pintype "passive"))
      (node (ref "D6") (pin "2") (pinfunction "A_2") (pintype "passive"))
      (node (ref "IC8") (pin "3") (pinfunction "RFOUT_3") (pintype "output"))
      (node (ref "L9") (pin "2") (pinfunction "2_2") (pintype "passive"))
    )
    (net (code "21") (name "Net-(IC8-RFIN)") (class "Default")
      (node (ref "C28") (pin "2") (pinfunction "2_2") (pintype "passive"))
      (node (ref "IC8") (pin "1") (pinfunction "RFIN_1") (pintype "input"))
    )
    (net (code "22") (name "Net-(IC9-COUPLED)") (class "Default")
      (node (ref "C48") (pin "2") (pinfunction "2_2") (pintype "passive"))
      (node (ref "IC9") (pin "1") (pinfunction "COUPLED_1") (pintype "bidirectional"))
      (node (ref "R58") (pin "2") (pinfunction "2_2") (pintype "passive"))
      (node (ref "R59") (pin "2") (pinfunction "2_2") (pintype "passive"))
    )
    (net (code "23") (name "Net-(IC9-OUT)") (class "Default")
      (node (ref "IC9") (pin "4") (pinfunction "OUT_4") (pintype "bidirectional"))
      (node (ref "R47") (pin "1") (pinfunction "1_1") (pintype "passive"))
      (node (ref "R48") (pin "1") (pinfunction "1_1") (pintype "passive"))
    )
    (net (code "24") (name "Net-(IC9-TERM)") (class "Default")
      (node (ref "IC9") (pin "6") (pinfunction "TERM_6") (pintype "passive"))
      (node (ref "R53") (pin "2") (pinfunction "2_2") (pintype "passive"))
      (node (ref "R54") (pin "2") (pinfunction "2_2") (pintype "passive"))
    )
    (net (code "25") (name "Net-(IC10-RF_IN)") (class "Default")
      (node (ref "C43") (pin "2") (pinfunction "2_2") (pintype "passive"))
      (node (ref "C49") (pin "2") (pinfunction "2_2") (pintype "passive"))
      (node (ref "IC10") (pin "1") (pinfunction "RF_IN_1") (pintype "input"))
      (node (ref "R55") (pin "1") (pinfunction "1_1") (pintype "passive"))
    )
    (net (code "26") (name "Net-(IC10-RF_OUT)") (class "Default")
      (node (ref "C44") (pin "2") (pinfunction "2_2") (pintype "passive"))
      (node (ref "C50") (pin "1") (pinfunction "1_1") (pintype "passive"))
      (node (ref "IC10") (pin "3") (pinfunction "RF_OUT_3") (pintype "output"))
      (node (ref "L5") (pin "2") (pinfunction "2_2") (pintype "passive"))
    )
    (net (code "27") (name "Net-(IC11-~{ERR})") (class "Default")
      (node (ref "IC11") (pin "6") (pinfunction "~{ERR}_6") (pintype "output"))
      (node (ref "R62") (pin "1") (pinfunction "1_1") (pintype "passive"))
    )
    (net (code "28") (name "Net-(IC12-CRMS)") (class "Default")
      (node (ref "C61") (pin "1") (pinfunction "1_1") (pintype "passive"))
      (node (ref "IC12") (pin "9") (pinfunction "CRMS_9") (pintype "input"))
    )
    (net (code "29") (name "Net-(IC12-DECL)") (class "Default")
      (node (ref "C61") (pin "2") (pinfunction "2_2") (pintype "passive"))
      (node (ref "IC12") (pin "4") (pinfunction "DECL_4") (pintype "input"))
      (node (ref "R75") (pin "2") (pinfunction "2_2") (pintype "passive"))
    )
    (net (code "30") (name "Net-(IC12-ENBL)") (class "Default")
      (node (ref "IC12") (pin "14") (pinfunction "ENBL_14") (pintype "input"))
      (node (ref "R64") (pin "2") (pinfunction "2_2") (pintype "passive"))
    )
    (net (code "31") (name "Net-(IC12-Q)") (class "Default")
      (node (ref "IC12") (pin "12") (pinfunction "Q_12") (pintype "output"))
      (node (ref "R71") (pin "2") (pinfunction "2_2") (pintype "passive"))
    )
    (net (code "32") (name "Net-(IC12-RFIN)") (class "Default")
      (node (ref "C48") (pin "1") (pinfunction "1_1") (pintype "passive"))
      (node (ref "IC12") (pin "1") (pinfunction "RFIN_1") (pintype "input"))
    )
    (net (code "33") (name "Net-(IC12-RST)") (class "Default")
      (node (ref "C56") (pin "1") (pinfunction "1_1") (pintype "passive"))
      (node (ref "IC12") (pin "15") (pinfunction "RST_15") (pintype "input"))
      (node (ref "R65") (pin "2") (pinfunction "2_2") (pintype "passive"))
      (node (ref "R66") (pin "2") (pinfunction "2_2") (pintype "passive"))
    )
    (net (code "34") (name "Net-(IC12-VIN-)") (class "Default")
      (node (ref "C58") (pin "2") (pinfunction "2_2") (pintype "passive"))
      (node (ref "IC12") (pin "16") (pinfunction "VIN-_16") (pintype "input"))
      (node (ref "R69") (pin "2") (pinfunction "2_2") (pintype "passive"))
      (node (ref "R73") (pin "1") (pinfunction "1_1") (pintype "passive"))
    )
    (net (code "35") (name "Net-(IC12-VRMS)") (class "Default")
      (node (ref "IC12") (pin "10") (pinfunction "VRMS_10") (pintype "output"))
      (node (ref "R74") (pin "2") (pinfunction "2_2") (pintype "passive"))
    )
    (net (code "36") (name "Net-(IC12-~{Q})") (class "Default")
      (node (ref "IC12") (pin "13") (pinfunction "~{Q}_13") (pintype "output"))
      (node (ref "R72") (pin "1") (pinfunction "1_1") (pintype "passive"))
    )
    (net (code "37") (name "Net-(IC13-IN+)") (class "Default")
      (node (ref "C59") (pin "2") (pinfunction "2_2") (pintype "passive"))
      (node (ref "IC13") (pin "3") (pinfunction "IN+_3") (pintype "input"))
      (node (ref "R74") (pin "1") (pinfunction "1_1") (pintype "passive"))
    )
    (net (code "38") (name "Net-(IC13-IN-)") (class "Default")
      (node (ref "IC13") (pin "4") (pinfunction "IN-_4") (pintype "input"))
      (node (ref "R67") (pin "2") (pinfunction "2_2") (pintype "passive"))
      (node (ref "R68") (pin "2") (pinfunction "2_2") (pintype "passive"))
    )
    (net (code "39") (name "Net-(IC13-OUT)") (class "Default")
      (node (ref "IC13") (pin "1") (pinfunction "OUT_1") (pintype "output"))
      (node (ref "R67") (pin "1") (pinfunction "1_1") (pintype "passive"))
      (node (ref "R70") (pin "1") (pinfunction "1_1") (pintype "passive"))
    )
    (net (code "40") (name "Net-(IC13-V+)") (class "Default")
      (node (ref "C57") (pin "2") (pinfunction "2_2") (pintype "passive"))
      (node (ref "IC13") (pin "5") (pinfunction "V+_5") (pintype "power_in"))
      (node (ref "L12") (pin "1") (pinfunction "1_1") (pintype "passive"))
    )
    (net (code "41") (name "Net-(IC14-A)") (class "Default")
      (node (ref "IC14") (pin "6") (pinfunction "A_6") (pintype "input"))
      (node (ref "R43") (pin "1") (pinfunction "1_1") (pintype "passive"))
    )
    (net (code "42") (name "Net-(IC14-B)") (class "Default")
      (node (ref "IC14") (pin "4") (pinfunction "B_4") (pintype "input"))
      (node (ref "R44") (pin "1") (pinfunction "1_1") (pintype "passive"))
    )
    (net (code "43") (name "Net-(IC14-RF1)") (class "Default")
      (node (ref "C42") (pin "2") (pinfunction "2_2") (pintype "passive"))
      (node (ref "IC14") (pin "3") (pinfunction "RF1_3") (pintype "bidirectional"))
    )
    (net (code "44") (name "Net-(IC14-RF2)") (class "Default")
      (node (ref "C34") (pin "2") (pinfunction "2_2") (pintype "passive"))
      (node (ref "IC14") (pin "1") (pinfunction "RF2_1") (pintype "bidirectional"))
    )
    (net (code "45") (name "Net-(IC14-RFC)") (class "Default")
      (node (ref "C39") (pin "1") (pinfunction "1_1") (pintype "passive"))
      (node (ref "IC14") (pin "5") (pinfunction "RFC_5") (pintype "bidirectional"))
    )
    (net (code "46") (name "Net-(J3-Pad1)") (class "Default")
      (node (ref "J3") (pin "1") (pinfunction "1_1") (pintype "bidirectional"))
      (node (ref "R50") (pin "1") (pinfunction "1_1") (pintype "passive"))
    )
    (net (code "47") (name "Net-(J4-Pad1)") (class "Default")
      (node (ref "J4") (pin "1") (pinfunction "1_1") (pintype "bidirectional"))
      (node (ref "R51") (pin "1") (pinfunction "1_1") (pintype "passive"))
    )
    (net (code "48") (name "Net-(P7-Pad5)") (class "Default")
      (node (ref "P7") (pin "5") (pinfunction "5_5") (pintype "passive"))
      (node (ref "R70") (pin "2") (pinfunction "2_2") (pintype "passive"))
    )
    (net (code "49") (name "P3V3A") (class "Default")
      (node (ref "C51") (pin "1") (pinfunction "1_1") (pintype "passive"))
      (node (ref "IC11") (pin "4") (pinfunction "OUT_4") (pintype "power_in"))
      (node (ref "L12") (pin "2") (pinfunction "2_2") (pintype "passive"))
      (node (ref "R62") (pin "2") (pinfunction "2_2") (pintype "passive"))
      (node (ref "R63") (pin "1") (pinfunction "1_1") (pintype "passive"))
    )
    (net (code "50") (name "P3V3ADL") (class "Default")
      (node (ref "C53") (pin "2") (pinfunction "2_2") (pintype "passive"))
      (node (ref "C54") (pin "2") (pinfunction "2_2") (pintype "passive"))
      (node (ref "C55") (pin "2") (pinfunction "2_2") (pintype "passive"))
      (node (ref "IC12") (pin "5") (pinfunction "VPOS_5") (pintype "power_in"))
      (node (ref "IC12") (pin "7") (pinfunction "VPOS_7") (pintype "power_in"))
      (node (ref "R63") (pin "2") (pinfunction "2_2") (pintype "passive"))
      (node (ref "R64") (pin "1") (pinfunction "1_1") (pintype "passive"))
    )
    (net (code "51") (name "VCC_PREAMP") (class "Default")
      (node (ref "L11") (pin "2") (pinfunction "2_2") (pintype "passive"))
      (node (ref "L8") (pin "1") (pinfunction "1_1") (pintype "passive"))
      (node (ref "P8") (pin "2") (pinfunction "2_2") (pintype "passive"))
    )
    (net (code "52") (name "VCC_PREAMP_1") (class "Default")
      (node (ref "C18") (pin "2") (pinfunction "2_2") (pintype "passive"))
      (node (ref "C52") (pin "2") (pinfunction "2_2") (pintype "passive"))
      (node (ref "IC11") (pin "3") (pinfunction "~{SD}_3") (pintype "input"))
      (node (ref "IC11") (pin "5") (pinfunction "IN_5") (pintype "input"))
      (node (ref "P7") (pin "8") (pinfunction "8_8") (pintype "passive"))
    )
    (net (code "53") (name "unconnected-(IC9-NU-Pad5)") (class "Default")
      (node (ref "IC9") (pin "5") (pinfunction "NU_5") (pintype "passive"))
    )
    (net (code "54") (name "unconnected-(IC11-NR-Pad2)") (class "Default")
      (node (ref "IC11") (pin "2") (pinfunction "NR_2") (pintype "input+no_connect"))
    )
    (net (code "55") (name "unconnected-(IC12-DNC-Pad2)") (class "Default")
      (node (ref "IC12") (pin "2") (pinfunction "DNC_2") (pintype "passive+no_connect"))
    )
    (net (code "56") (name "unconnected-(IC12-DNC-Pad6)") (class "Default")
      (node (ref "IC12") (pin "6") (pinfunction "DNC_6") (pintype "passive+no_connect"))
    )
    (net (code "57") (name "unconnected-(IC12-DNC-Pad8)") (class "Default")
      (node (ref "IC12") (pin "8") (pinfunction "DNC_8") (pintype "passive+no_connect"))
    )
    (net (code "58") (name "unconnected-(IC12-VCAL-Pad3)") (class "Default")
      (node (ref "IC12") (pin "3") (pinfunction "VCAL_3") (pintype "input+no_connect"))
    )
    (net (code "59") (name "unconnected-(P7-Pad2)") (class "Default")
      (node (ref "P7") (pin "2") (pinfunction "2_2") (pintype "passive+no_connect"))
    )
    (net (code "60") (name "unconnected-(P7-Pad4)") (class "Default")
      (node (ref "P7") (pin "4") (pinfunction "4_4") (pintype "passive+no_connect"))
    )
    (net (code "61") (name "unconnected-(P8-Pad3)") (class "Default")
      (node (ref "P8") (pin "3") (pinfunction "3_3") (pintype "passive+no_connect"))
    )
    (net (code "62") (name "unconnected-(P8-Pad4)") (class "Default")
      (node (ref "P8") (pin "4") (pinfunction "4_4") (pintype "passive+no_connect"))
    )
    (net (code "63") (name "unconnected-(P8-Pad5)") (class "Default")
      (node (ref "P8") (pin "5") (pinfunction "5_5") (pintype "passive+no_connect"))
    )
    (net (code "64") (name "unconnected-(P8-Pad6)") (class "Default")
      (node (ref "P8") (pin "6") (pinfunction "6_6") (pintype "passive+no_connect"))
    )
  )
)
